# LED_BRD.net
KiCad netlist of a schematic drawn in EAGLE
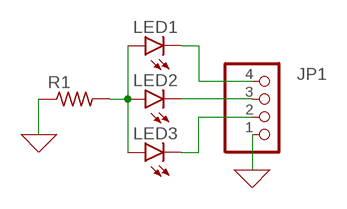
[diagram p0: schematic, sheet 1]

(export (version "E")
  (design (tool "Eeschema 10.0.6"))
  (components
    (comp (ref "JP1")
      (value "PINHD-1X4")
      (footprint "eagle-import:1X04")
      (libsource (lib "eagle-import") (part "PINHD-1X4"))
    )
    (comp (ref "LED1")
      (value "LED5MM")
      (footprint "eagle-import:LED5MM")
      (libsource (lib "eagle-import") (part "LED5MM"))
    )
    (comp (ref "LED2")
      (value "LED5MM")
      (footprint "eagle-import:LED5MM")
      (libsource (lib "eagle-import") (part "LED5MM"))
    )
    (comp (ref "LED3")
      (value "LED5MM")
      (footprint "eagle-import:LED5MM")
      (libsource (lib "eagle-import") (part "LED5MM"))
    )
    (comp (ref "R1")
      (value "R-US_0204/7")
      (footprint "eagle-import:0204_7")
      (libsource (lib "eagle-import") (part "R-US_0204/7"))
    )
  )
  (nets
    (net (code "1") (name "GND") (class "Default")
      (node (ref "JP1") (pin "1") (pinfunction "1_1") (pintype "passive"))
      (node (ref "R1") (pin "1") (pinfunction "1_1") (pintype "passive"))
    )
    (net (code "2") (name "Net-(LED1-C)") (class "Default")
      (node (ref "JP1") (pin "4") (pinfunction "4_4") (pintype "passive"))
      (node (ref "LED1") (pin "K") (pinfunction "C_K") (pintype "passive"))
    )
    (net (code "3") (name "Net-(LED1-PadA)") (class "Default")
      (node (ref "LED1") (pin "A") (pinfunction "A_A") (pintype "passive"))
      (node (ref "LED2") (pin "A") (pinfunction "A_A") (pintype "passive"))
      (node (ref "LED3") (pin "A") (pinfunction "A_A") (pintype "passive"))
      (node (ref "R1") (pin "2") (pinfunction "2_2") (pintype "passive"))
    )
    (net (code "4") (name "Net-(LED2-C)") (class "Default")
      (node (ref "JP1") (pin "3") (pinfunction "3_3") (pintype "passive"))
      (node (ref "LED2") (pin "K") (pinfunction "C_K") (pintype "passive"))
    )
    (net (code "5") (name "Net-(LED3-C)") (class "Default")
      (node (ref "JP1") (pin "2") (pinfunction "2_2") (pintype "passive"))
      (node (ref "LED3") (pin "K") (pinfunction "C_K") (pintype "passive"))
    )
  )
)
